# Memory-A2.net
KiCad netlist of a schematic drawn in Altium Designer
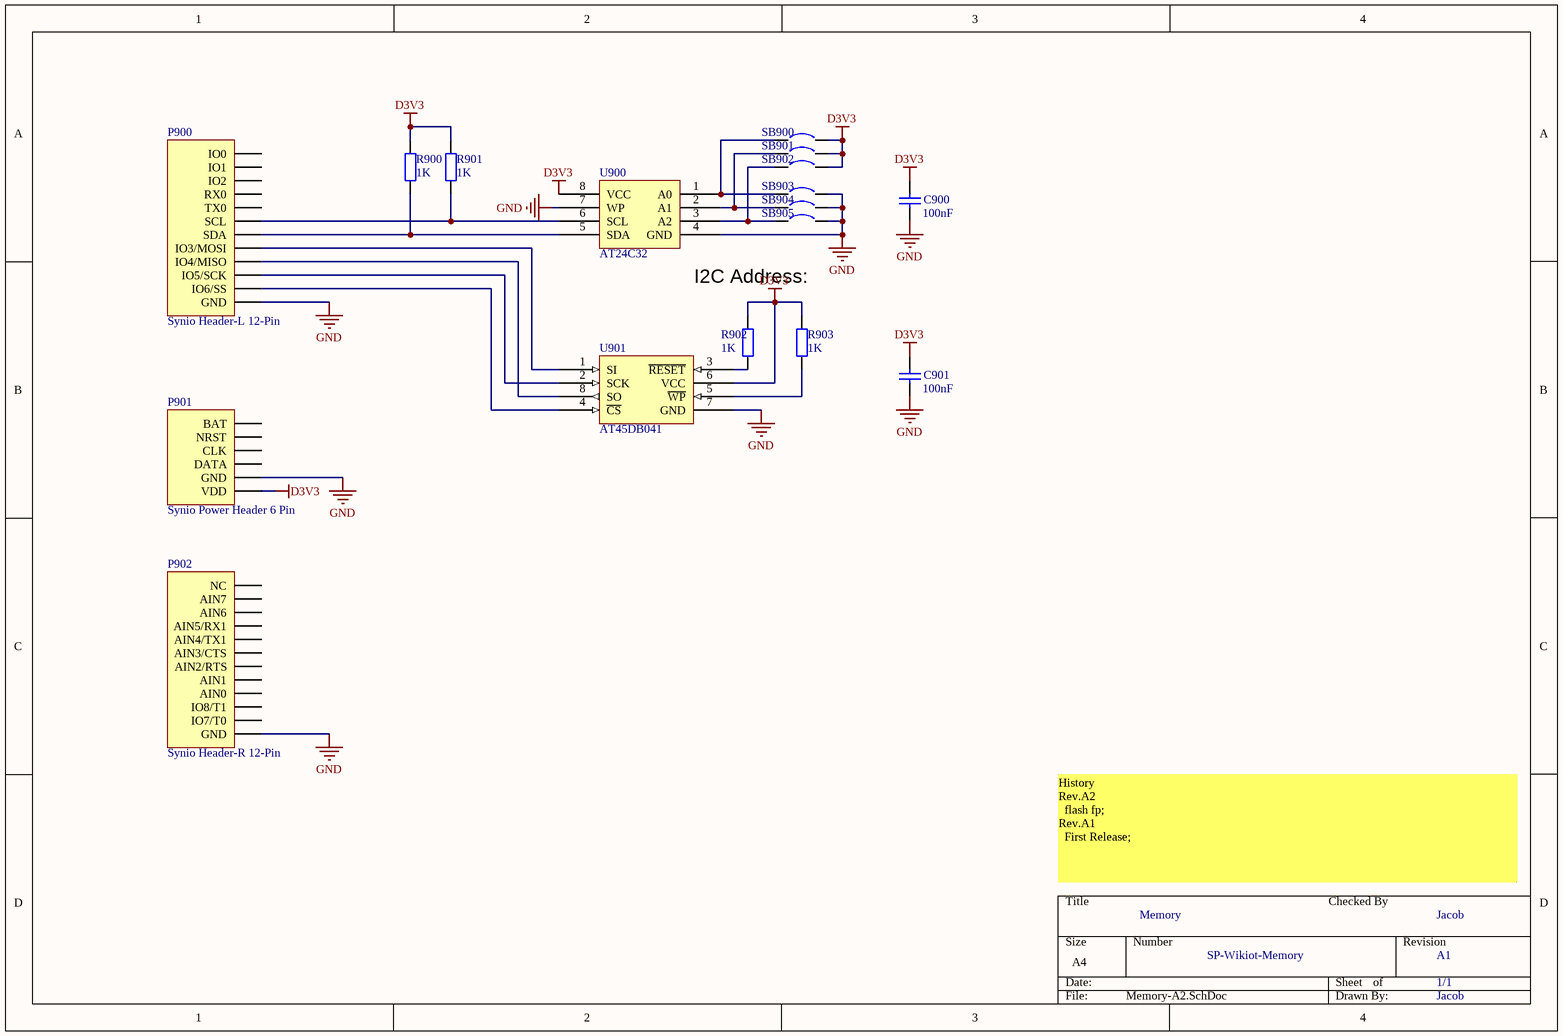
[diagram p0: Memory-A2.SchDoc]

(export (version "E")
  (design (tool "Eeschema 10.0.6"))
  (components
    (comp (ref "C900")
      (value "100nF")
      (footprint "C0603L")
      (description "Capacitor")
      (fields (field (name "PUBLISHER") "Altium Limited"))
      (libsource (lib "Miscellaneous Devices") (part "Cap"))
    )
    (comp (ref "C901")
      (value "100nF")
      (footprint "C0603L")
      (description "Capacitor")
      (fields (field (name "PUBLISHER") "Altium Limited"))
      (libsource (lib "Miscellaneous Devices") (part "Cap"))
    )
    (comp (ref "P900")
      (value "Synio Header-L 12-Pin")
      (footprint "HDR1X12/2.54MM")
      (description "Synio Header-L, 12-Pin")
      (fields (field (name "PUBLISHER") "Altium Limited"))
      (libsource (lib "Connector") (part "Synio Header-L 12-Pin"))
    )
    (comp (ref "P901")
      (value "Synio Power Header 6 Pin")
      (footprint "HDR1X6/2.54MM")
      (libsource (lib "Connector") (part "Synio Power Header 6 Pin"))
    )
    (comp (ref "P902")
      (value "Synio Header-R 12-Pin")
      (footprint "HDR1X12/2.54MM")
      (description "Synio Header-R, 12-Pin")
      (fields (field (name "PUBLISHER") "Altium Limited"))
      (libsource (lib "Connector") (part "Synio Header-R 12-Pin"))
    )
    (comp (ref "R900")
      (value "1K")
      (footprint "R0603")
      (description "Resistor")
      (fields (field (name "PUBLISHER") "Altium Limited"))
      (libsource (lib "Miscellaneous Devices") (part "Res2"))
    )
    (comp (ref "R901")
      (value "1K")
      (footprint "R0603")
      (description "Resistor")
      (fields (field (name "PUBLISHER") "Altium Limited"))
      (libsource (lib "Miscellaneous Devices") (part "Res2"))
    )
    (comp (ref "R902")
      (value "1K")
      (footprint "R0603")
      (description "Resistor")
      (fields (field (name "PUBLISHER") "Altium Limited"))
      (libsource (lib "") (part "Res2_1"))
    )
    (comp (ref "R903")
      (value "1K")
      (footprint "R0603")
      (description "Resistor")
      (fields (field (name "PUBLISHER") "Altium Limited"))
      (libsource (lib "") (part "Res2_1"))
    )
    (comp (ref "SB900")
      (value "Circuit Breaker")
      (footprint "JP2_SMD")
      (fields (field (name "PUBLISHER") "Altium Limited"))
      (libsource (lib "Misc") (part "Circuit Breaker"))
    )
    (comp (ref "SB901")
      (value "Circuit Breaker")
      (footprint "JP2_SMD")
      (fields (field (name "PUBLISHER") "Altium Limited"))
      (libsource (lib "Misc") (part "Circuit Breaker"))
    )
    (comp (ref "SB902")
      (value "Circuit Breaker")
      (footprint "JP2_SMD")
      (fields (field (name "PUBLISHER") "Altium Limited"))
      (libsource (lib "Misc") (part "Circuit Breaker"))
    )
    (comp (ref "SB903")
      (value "Circuit Breaker")
      (footprint "JP2_SMD")
      (fields (field (name "PUBLISHER") "Altium Limited"))
      (libsource (lib "Misc") (part "Circuit Breaker"))
    )
    (comp (ref "SB904")
      (value "Circuit Breaker")
      (footprint "JP2_SMD")
      (fields (field (name "PUBLISHER") "Altium Limited"))
      (libsource (lib "Misc") (part "Circuit Breaker"))
    )
    (comp (ref "SB905")
      (value "Circuit Breaker")
      (footprint "JP2_SMD")
      (fields (field (name "PUBLISHER") "Altium Limited"))
      (libsource (lib "Misc") (part "Circuit Breaker"))
    )
    (comp (ref "U900")
      (value "AT24C32")
      (footprint "SO8W_M")
      (description "IIC EEPROM")
      (libsource (lib "Logic") (part "At24CXX"))
    )
    (comp (ref "U901")
      (value "AT45DB041")
      (footprint "SO8_N")
      (description "4M Serial Flash")
      (libsource (lib "Logic") (part "AT45DB041"))
    )
  )
  (nets
    (net (code "1") (name "D3V3") (class "Default")
      (node (ref "C900") (pin "1") (pinfunction "1_1") (pintype "passive"))
      (node (ref "C901") (pin "1") (pinfunction "1_1") (pintype "passive"))
      (node (ref "P901") (pin "1") (pinfunction "VDD_1") (pintype "passive"))
      (node (ref "R900") (pin "2") (pinfunction "2_2") (pintype "passive"))
      (node (ref "R901") (pin "2") (pinfunction "2_2") (pintype "passive"))
      (node (ref "R902") (pin "1") (pinfunction "1_1") (pintype "passive"))
      (node (ref "R903") (pin "1") (pinfunction "1_1") (pintype "passive"))
      (node (ref "SB900") (pin "2") (pinfunction "2_2") (pintype "passive"))
      (node (ref "SB901") (pin "2") (pinfunction "2_2") (pintype "passive"))
      (node (ref "SB902") (pin "2") (pinfunction "2_2") (pintype "passive"))
      (node (ref "U900") (pin "8") (pinfunction "VCC_8") (pintype "passive"))
      (node (ref "U901") (pin "6") (pinfunction "VCC_6") (pintype "power_in"))
    )
    (net (code "2") (name "GND") (class "Default")
      (node (ref "C900") (pin "2") (pinfunction "2_2") (pintype "passive"))
      (node (ref "C901") (pin "2") (pinfunction "2_2") (pintype "passive"))
      (node (ref "P900") (pin "1") (pinfunction "GND_1") (pintype "passive"))
      (node (ref "P901") (pin "2") (pinfunction "GND_2") (pintype "passive"))
      (node (ref "P902") (pin "1") (pinfunction "GND_1") (pintype "passive"))
      (node (ref "SB903") (pin "2") (pinfunction "2_2") (pintype "passive"))
      (node (ref "SB904") (pin "2") (pinfunction "2_2") (pintype "passive"))
      (node (ref "SB905") (pin "2") (pinfunction "2_2") (pintype "passive"))
      (node (ref "U900") (pin "4") (pinfunction "GND_4") (pintype "passive"))
      (node (ref "U900") (pin "7") (pinfunction "WP_7") (pintype "passive"))
      (node (ref "U901") (pin "7") (pinfunction "GND_7") (pintype "power_in"))
    )
    (net (code "3") (name "Net-(P900-IO3{slash}MOSI)") (class "Default")
      (node (ref "P900") (pin "5") (pinfunction "IO3/MOSI_5") (pintype "passive"))
      (node (ref "U901") (pin "1") (pinfunction "SI_1") (pintype "input"))
    )
    (net (code "4") (name "Net-(P900-IO4{slash}MISO)") (class "Default")
      (node (ref "P900") (pin "4") (pinfunction "IO4/MISO_4") (pintype "passive"))
      (node (ref "U901") (pin "8") (pinfunction "SO_8") (pintype "output"))
    )
    (net (code "5") (name "Net-(P900-IO5{slash}SCK)") (class "Default")
      (node (ref "P900") (pin "3") (pinfunction "IO5/SCK_3") (pintype "passive"))
      (node (ref "U901") (pin "2") (pinfunction "SCK_2") (pintype "input"))
    )
    (net (code "6") (name "Net-(P900-IO6{slash}SS)") (class "Default")
      (node (ref "P900") (pin "2") (pinfunction "IO6/SS_2") (pintype "passive"))
      (node (ref "U901") (pin "4") (pinfunction "~{CS}_4") (pintype "input"))
    )
    (net (code "7") (name "Net-(P900-SCL)") (class "Default")
      (node (ref "P900") (pin "7") (pinfunction "SCL_7") (pintype "passive"))
      (node (ref "R901") (pin "1") (pinfunction "1_1") (pintype "passive"))
      (node (ref "U900") (pin "6") (pinfunction "SCL_6") (pintype "passive"))
    )
    (net (code "8") (name "Net-(P900-SDA)") (class "Default")
      (node (ref "P900") (pin "6") (pinfunction "SDA_6") (pintype "passive"))
      (node (ref "R900") (pin "1") (pinfunction "1_1") (pintype "passive"))
      (node (ref "U900") (pin "5") (pinfunction "SDA_5") (pintype "passive"))
    )
    (net (code "9") (name "Net-(U900-A0)") (class "Default")
      (node (ref "SB900") (pin "1") (pinfunction "1_1") (pintype "passive"))
      (node (ref "SB903") (pin "1") (pinfunction "1_1") (pintype "passive"))
      (node (ref "U900") (pin "1") (pinfunction "A0_1") (pintype "passive"))
    )
    (net (code "10") (name "Net-(U900-A1)") (class "Default")
      (node (ref "SB901") (pin "1") (pinfunction "1_1") (pintype "passive"))
      (node (ref "SB904") (pin "1") (pinfunction "1_1") (pintype "passive"))
      (node (ref "U900") (pin "2") (pinfunction "A1_2") (pintype "passive"))
    )
    (net (code "11") (name "Net-(U900-A2)") (class "Default")
      (node (ref "SB902") (pin "1") (pinfunction "1_1") (pintype "passive"))
      (node (ref "SB905") (pin "1") (pinfunction "1_1") (pintype "passive"))
      (node (ref "U900") (pin "3") (pinfunction "A2_3") (pintype "passive"))
    )
    (net (code "12") (name "Net-(U901-~{RESET})") (class "Default")
      (node (ref "R902") (pin "2") (pinfunction "2_2") (pintype "passive"))
      (node (ref "U901") (pin "3") (pinfunction "~{RESET}_3") (pintype "input"))
    )
    (net (code "13") (name "Net-(U901-~{WP})") (class "Default")
      (node (ref "R903") (pin "2") (pinfunction "2_2") (pintype "passive"))
      (node (ref "U901") (pin "5") (pinfunction "~{WP}_5") (pintype "input"))
    )
    (net (code "14") (name "unconnected-(P900-IO0-Pad12)") (class "Default")
      (node (ref "P900") (pin "12") (pinfunction "IO0_12") (pintype "passive"))
    )
    (net (code "15") (name "unconnected-(P900-IO1-Pad11)") (class "Default")
      (node (ref "P900") (pin "11") (pinfunction "IO1_11") (pintype "passive"))
    )
    (net (code "16") (name "unconnected-(P900-IO2-Pad10)") (class "Default")
      (node (ref "P900") (pin "10") (pinfunction "IO2_10") (pintype "passive"))
    )
    (net (code "17") (name "unconnected-(P900-RX0-Pad9)") (class "Default")
      (node (ref "P900") (pin "9") (pinfunction "RX0_9") (pintype "passive"))
    )
    (net (code "18") (name "unconnected-(P900-TX0-Pad8)") (class "Default")
      (node (ref "P900") (pin "8") (pinfunction "TX0_8") (pintype "passive"))
    )
    (net (code "19") (name "unconnected-(P901-BAT-Pad6)") (class "Default")
      (node (ref "P901") (pin "6") (pinfunction "BAT_6") (pintype "passive"))
    )
    (net (code "20") (name "unconnected-(P901-CLK-Pad4)") (class "Default")
      (node (ref "P901") (pin "4") (pinfunction "CLK_4") (pintype "passive"))
    )
    (net (code "21") (name "unconnected-(P901-DATA-Pad3)") (class "Default")
      (node (ref "P901") (pin "3") (pinfunction "DATA_3") (pintype "passive"))
    )
    (net (code "22") (name "unconnected-(P901-NRST-Pad5)") (class "Default")
      (node (ref "P901") (pin "5") (pinfunction "NRST_5") (pintype "passive"))
    )
    (net (code "23") (name "unconnected-(P902-AIN0-Pad4)") (class "Default")
      (node (ref "P902") (pin "4") (pinfunction "AIN0_4") (pintype "passive"))
    )
    (net (code "24") (name "unconnected-(P902-AIN1-Pad5)") (class "Default")
      (node (ref "P902") (pin "5") (pinfunction "AIN1_5") (pintype "passive"))
    )
    (net (code "25") (name "unconnected-(P902-AIN2{slash}RTS-Pad6)") (class "Default")
      (node (ref "P902") (pin "6") (pinfunction "AIN2/RTS_6") (pintype "passive"))
    )
    (net (code "26") (name "unconnected-(P902-AIN3{slash}CTS-Pad7)") (class "Default")
      (node (ref "P902") (pin "7") (pinfunction "AIN3/CTS_7") (pintype "passive"))
    )
    (net (code "27") (name "unconnected-(P902-AIN4{slash}TX1-Pad8)") (class "Default")
      (node (ref "P902") (pin "8") (pinfunction "AIN4/TX1_8") (pintype "passive"))
    )
    (net (code "28") (name "unconnected-(P902-AIN5{slash}RX1-Pad9)") (class "Default")
      (node (ref "P902") (pin "9") (pinfunction "AIN5/RX1_9") (pintype "passive"))
    )
    (net (code "29") (name "unconnected-(P902-AIN6-Pad10)") (class "Default")
      (node (ref "P902") (pin "10") (pinfunction "AIN6_10") (pintype "passive"))
    )
    (net (code "30") (name "unconnected-(P902-AIN7-Pad11)") (class "Default")
      (node (ref "P902") (pin "11") (pinfunction "AIN7_11") (pintype "passive"))
    )
    (net (code "31") (name "unconnected-(P902-IO7{slash}T0-Pad2)") (class "Default")
      (node (ref "P902") (pin "2") (pinfunction "IO7/T0_2") (pintype "passive"))
    )
    (net (code "32") (name "unconnected-(P902-IO8{slash}T1-Pad3)") (class "Default")
      (node (ref "P902") (pin "3") (pinfunction "IO8/T1_3") (pintype "passive"))
    )
    (net (code "33") (name "unconnected-(P902-NC-Pad12)") (class "Default")
      (node (ref "P902") (pin "12") (pinfunction "NC_12") (pintype "passive"))
    )
  )
)
